# button_brick.net
KiCad netlist of a schematic drawn in EAGLE
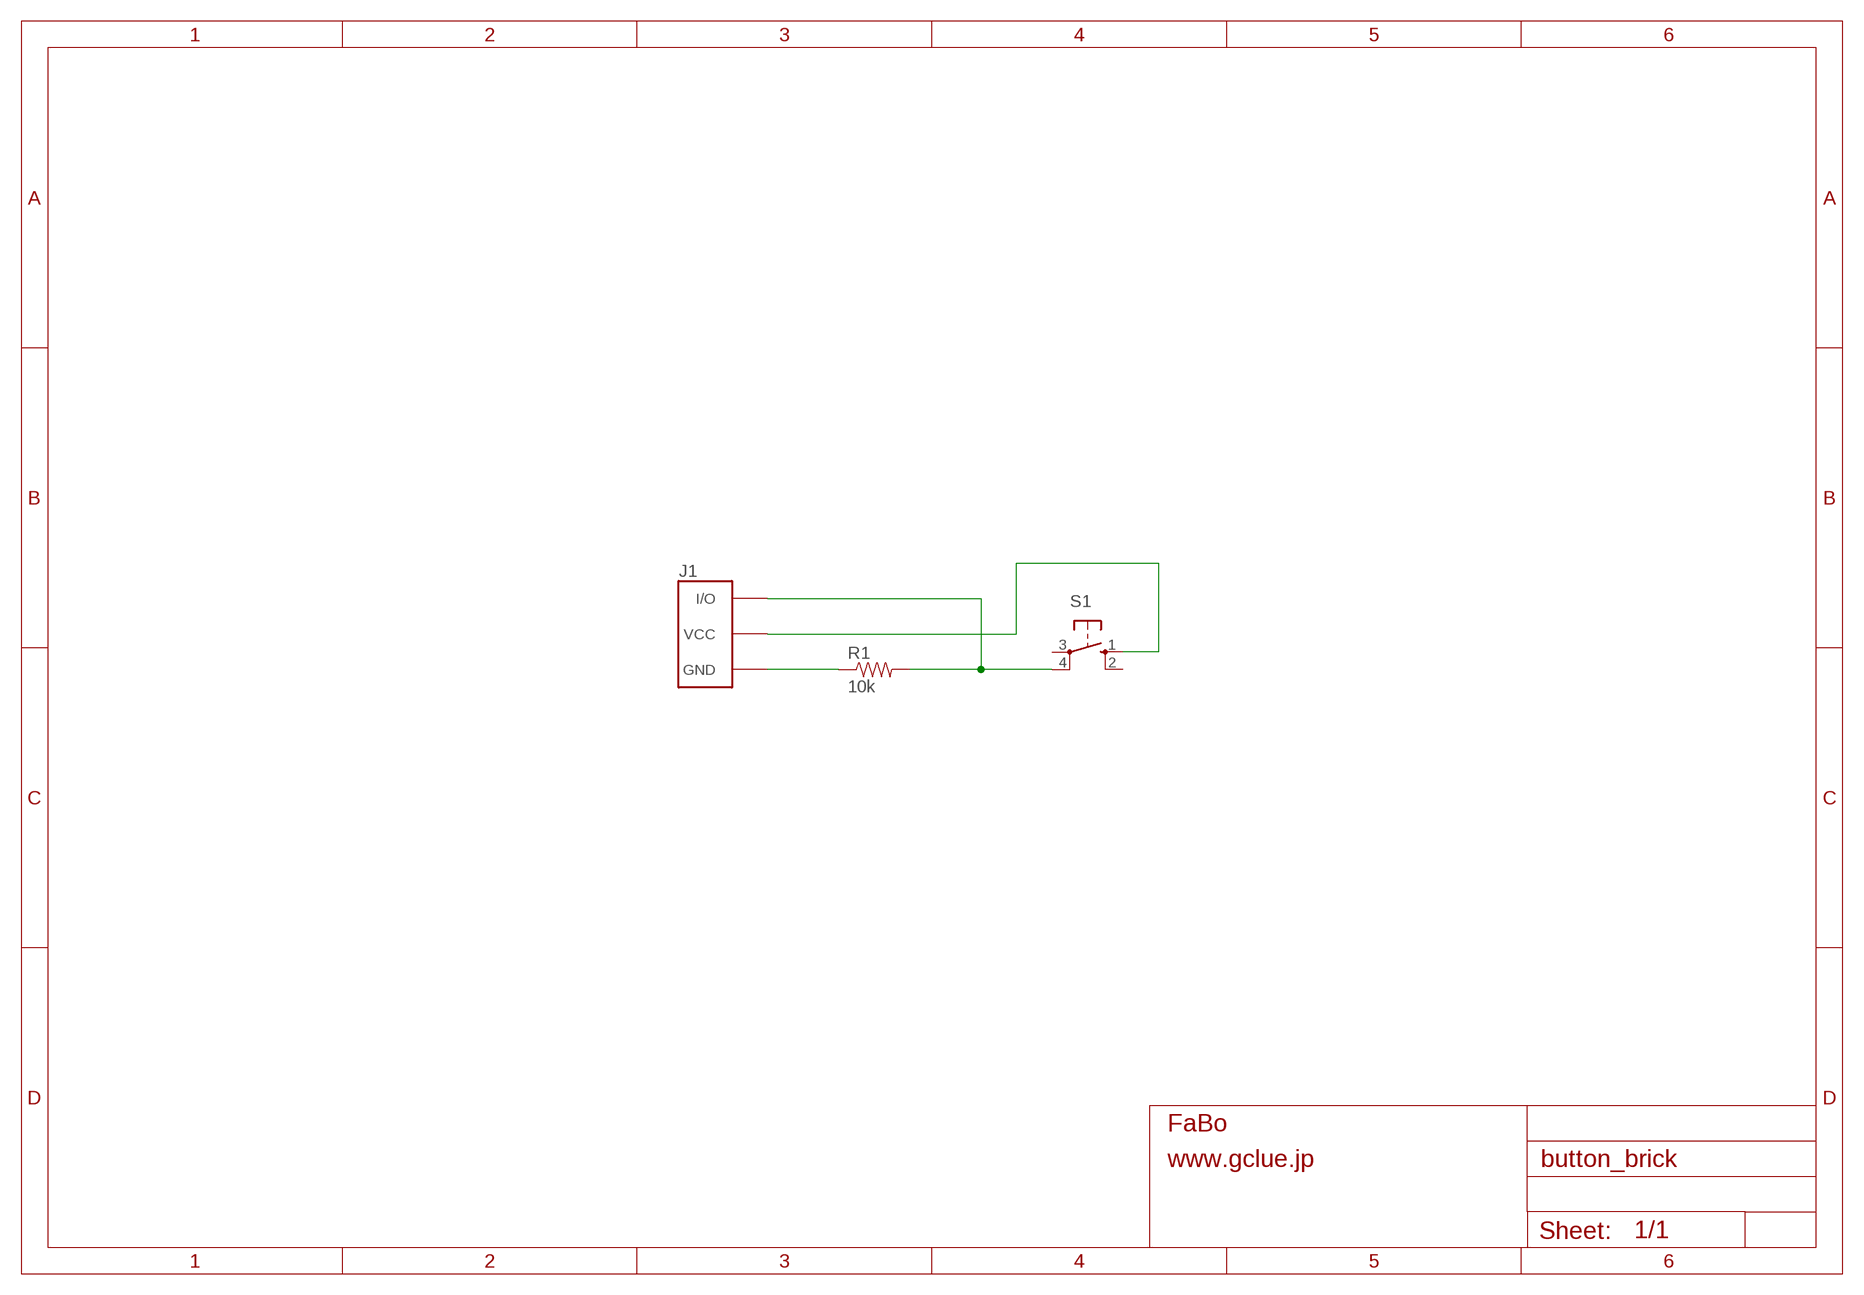
[diagram p0: schematic, sheet 1]

(export (version "E")
  (design (tool "Eeschema 10.0.6"))
  (components
    (comp (ref "J1")
      (value "BRICK_3PIN")
      (footprint "eagle-import:BRICK_3PIN")
      (libsource (lib "eagle-import") (part "BRICK_3PIN"))
    )
    (comp (ref "R1")
      (value "10k")
      (footprint "eagle-import:AXIAL-0.4")
      (libsource (lib "eagle-import") (part "RESISTORPTH-1/4W"))
    )
    (comp (ref "S1")
      (value "10-XX")
      (footprint "eagle-import:B3F-10XX")
      (fields (field (name "MPN") "B3F-1000"))
      (libsource (lib "eagle-import") (part "10-XX"))
    )
  )
  (nets
    (net (code "1") (name "Net-(J1-I{slash}O)") (class "Default")
      (node (ref "J1") (pin "IN/OUT") (pinfunction "I/O_IN/OUT") (pintype "bidirectional"))
      (node (ref "R1") (pin "P$2") (pinfunction "2_P$2") (pintype "passive"))
      (node (ref "S1") (pin "4") (pinfunction "P1_4") (pintype "passive"))
    )
    (net (code "2") (name "Net-(R1-1)") (class "Default")
      (node (ref "J1") (pin "GND") (pinfunction "GND_GND") (pintype "bidirectional"))
      (node (ref "R1") (pin "P$1") (pinfunction "1_P$1") (pintype "passive"))
    )
    (net (code "3") (name "Net-(S1-S)") (class "Default")
      (node (ref "J1") (pin "VCC") (pinfunction "VCC_VCC") (pintype "bidirectional"))
      (node (ref "S1") (pin "1") (pinfunction "S_1") (pintype "passive"))
    )
    (net (code "4") (name "unconnected-(S1-P-Pad3)") (class "Default")
      (node (ref "S1") (pin "3") (pinfunction "P_3") (pintype "passive"))
    )
    (net (code "5") (name "unconnected-(S1-S1-Pad2)") (class "Default")
      (node (ref "S1") (pin "2") (pinfunction "S1_2") (pintype "passive"))
    )
  )
)
